# Shematic_NANO.net
KiCad netlist of a schematic drawn in Altium Designer
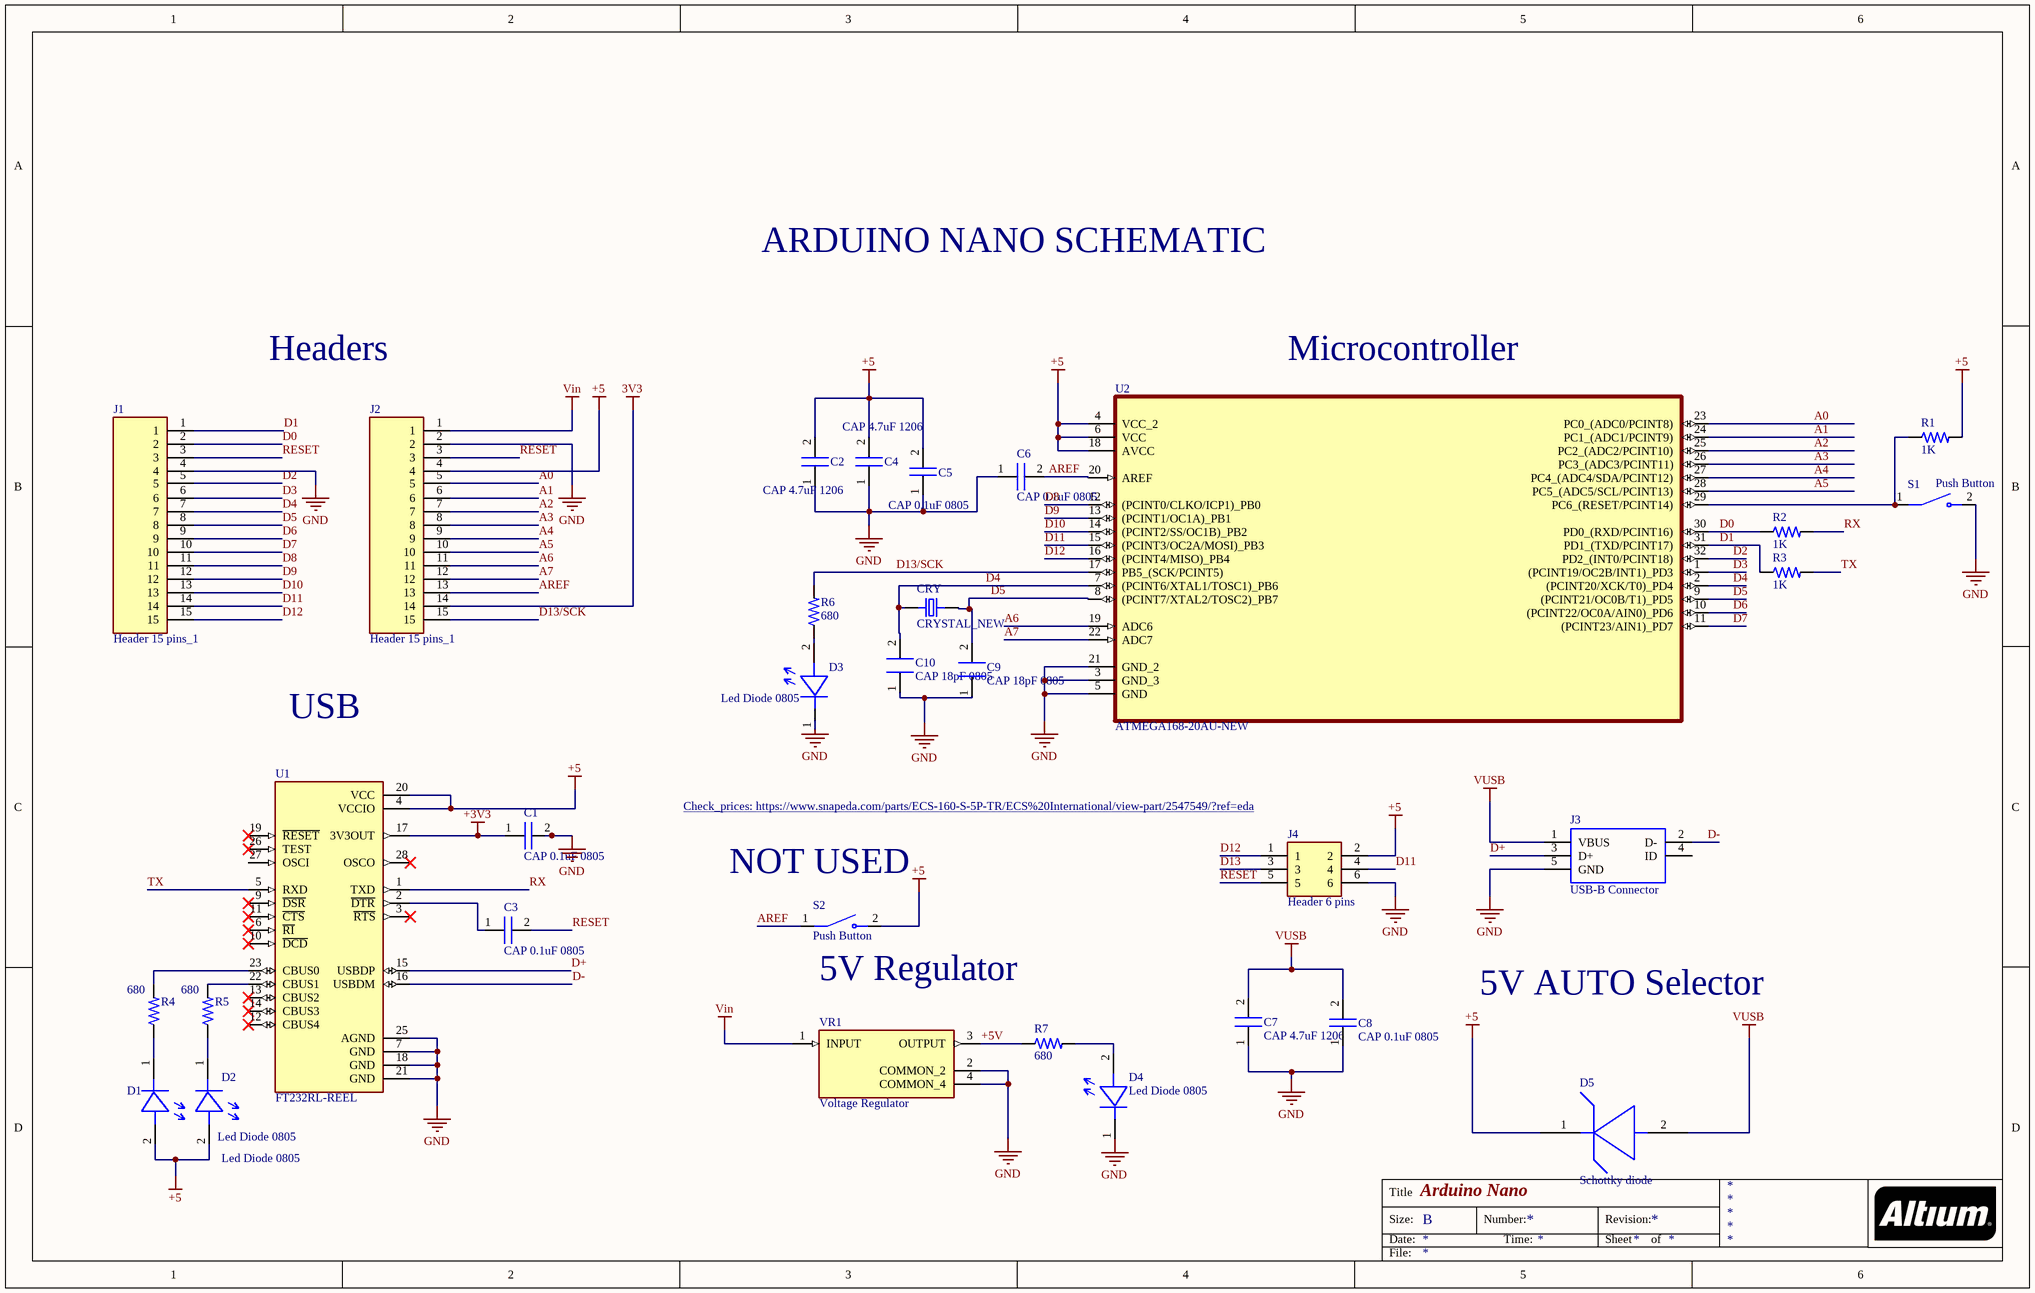
[diagram p0: Shematic_NANO.SchDoc]

(export (version "E")
  (design (tool "Eeschema 10.0.6"))
  (components
    (comp (ref "C1")
      (value "CAP 0.1uF 0805")
      (footprint "CAP 0.1uF 0805")
      (libsource (lib "Schlib1_NANO") (part "CAP 0.1uF 0805"))
    )
    (comp (ref "C2")
      (value "CAP 4.7uF 1206")
      (footprint "CAP 4.7 uF 1206")
      (libsource (lib "Schlib1_NANO") (part "CAP 4.7uF 1206"))
    )
    (comp (ref "C3")
      (value "CAP 0.1uF 0805")
      (footprint "CAP 0.1uF 0805")
      (libsource (lib "Schlib1_NANO") (part "CAP 0.1uF 0805"))
    )
    (comp (ref "C4")
      (value "CAP 4.7uF 1206")
      (footprint "CAP 4.7 uF 1206")
      (libsource (lib "Schlib1_NANO") (part "CAP 4.7uF 1206"))
    )
    (comp (ref "C5")
      (value "CAP 0.1uF 0805")
      (footprint "CAP 0.1uF 0805")
      (libsource (lib "Schlib1_NANO") (part "CAP 0.1uF 0805"))
    )
    (comp (ref "C6")
      (value "CAP 0.1uF 0805")
      (footprint "CAP 0.1uF 0805")
      (libsource (lib "Schlib1_NANO") (part "CAP 0.1uF 0805"))
    )
    (comp (ref "C7")
      (value "CAP 4.7uF 1206")
      (footprint "CAP 4.7 uF 1206")
      (libsource (lib "Schlib1_NANO") (part "CAP 4.7uF 1206"))
    )
    (comp (ref "C8")
      (value "CAP 0.1uF 0805")
      (footprint "CAP 0.1uF 0805")
      (libsource (lib "Schlib1_NANO") (part "CAP 0.1uF 0805"))
    )
    (comp (ref "C9")
      (value "CAP 18pF 0805")
      (footprint "CAP 18pF 0805")
      (libsource (lib "Schlib1_NANO") (part "CAP 18pF 0805"))
    )
    (comp (ref "C10")
      (value "CAP 18pF 0805")
      (footprint "CAP 18pF 0805")
      (libsource (lib "Schlib1_NANO") (part "CAP 18pF 0805"))
    )
    (comp (ref "CRY")
      (value "CRYSTAL_NEW")
      (footprint "CRYSTAL 16MHZ")
      (description "16MHz Â±30ppm Crystal Series 40 Ohms HC-49/US")
      (fields
        (field (name "MF") "ECS International")
        (field (name "MP") "ECS-160-S-5P-TR")
        (field (name "CHECK_PRICES") "https://www.snapeda.com/parts/ECS-160-S-5P-TR/ECS%20International/view-part/2547549/?ref=eda")
      )
      (libsource (lib "Schlib1_NANO") (part "CRYSTAL_NEW"))
    )
    (comp (ref "D1")
      (value "Led Diode 0805")
      (footprint "LED 0805")
      (libsource (lib "Schlib1_NANO") (part "Led Diode 0805"))
    )
    (comp (ref "D2")
      (value "Led Diode 0805")
      (footprint "LED 0805")
      (libsource (lib "Schlib1_NANO") (part "Led Diode 0805"))
    )
    (comp (ref "D3")
      (value "Led Diode 0805")
      (footprint "LED 0805")
      (libsource (lib "Schlib1_NANO") (part "Led Diode 0805"))
    )
    (comp (ref "D4")
      (value "Led Diode 0805")
      (footprint "LED 0805")
      (libsource (lib "Schlib1_NANO") (part "Led Diode 0805"))
    )
    (comp (ref "D5")
      (value "Schottky diode")
      (footprint "Schottky diode")
      (description "Schottky diode 0.5A 20V")
      (libsource (lib "Schlib1_NANO") (part "Schottky diode"))
    )
    (comp (ref "J1")
      (value "Header 15 pins_1")
      (footprint "Header 15 pins")
      (fields (field (name "MP") "4-644456-5"))
      (libsource (lib "Schlib1_NANO") (part "Header 15 pins_1"))
    )
    (comp (ref "J2")
      (value "Header 15 pins_1")
      (footprint "Header 15 pins")
      (fields (field (name "MP") "4-644456-5"))
      (libsource (lib "Schlib1_NANO") (part "Header 15 pins_1"))
    )
    (comp (ref "J3")
      (value "USB-B Connector")
      (footprint "USB-B Connector")
      (description "USB - mini B USB 2.0 OTG Receptacle Connector 5 Position Surface Mount, Right Angle")
      (fields (field (name "MF") "Molex") (field (name "MP") "67503-1020"))
      (libsource (lib "Schlib1_NANO") (part "USB-B Connector"))
    )
    (comp (ref "J4")
      (value "Header 6 pins")
      (footprint "Header 6 pins")
      (description "Connector Header Through Hole 6 position 0.100 _2.54mm_")
      (fields (field (name "MF") "Amphenol ICC") (field (name "DIGI-KEY_PART_NUMBER") "609-3234-ND"))
      (libsource (lib "Schlib1_NANO") (part "Header 6 pins"))
    )
    (comp (ref "R1")
      (value "1K")
      (footprint "RES 0402")
      (description "RL73H 2B R10 1% 5K RL")
      (fields (field (name "MP") "1-1879462-1"))
      (libsource (lib "Schlib1_NANO") (part "RES 1206"))
    )
    (comp (ref "R2")
      (value "1K")
      (footprint "RES 0402")
      (description "RL73H 2B R10 1% 5K RL")
      (fields (field (name "MP") "1-1879462-1"))
      (libsource (lib "Schlib1_NANO") (part "RES 1206"))
    )
    (comp (ref "R3")
      (value "1K")
      (footprint "RES 0402")
      (description "RL73H 2B R10 1% 5K RL")
      (fields (field (name "MP") "1-1879462-1"))
      (libsource (lib "Schlib1_NANO") (part "RES 1206"))
    )
    (comp (ref "R4")
      (value "680")
      (footprint "RES 0402")
      (description "RL73H 2B R10 1% 5K RL")
      (fields (field (name "MP") "1-1879462-1"))
      (libsource (lib "Schlib1_NANO") (part "RES 1206"))
    )
    (comp (ref "R5")
      (value "680")
      (footprint "RES 0402")
      (description "RL73H 2B R10 1% 5K RL")
      (fields (field (name "MP") "1-1879462-1"))
      (libsource (lib "Schlib1_NANO") (part "RES 1206"))
    )
    (comp (ref "R6")
      (value "680")
      (footprint "RES 0402")
      (description "RL73H 2B R10 1% 5K RL")
      (fields (field (name "MP") "1-1879462-1"))
      (libsource (lib "Schlib1_NANO") (part "RES 1206"))
    )
    (comp (ref "R7")
      (value "680")
      (footprint "RES 0402")
      (description "RL73H 2B R10 1% 5K RL")
      (fields (field (name "MP") "1-1879462-1"))
      (libsource (lib "Schlib1_NANO") (part "RES 1206"))
    )
    (comp (ref "S1")
      (value "Push Button")
      (footprint "Push Button")
      (description "Switch Tactile N.O. SPST Round Button Gull Wing 0.05A 12VDC 1.5N SMD Embossed T/R")
      (fields (field (name "MP") "B3U-1000P"))
      (libsource (lib "Schlib1_NANO") (part "Push Button"))
    )
    (comp (ref "S2")
      (value "Push Button")
      (footprint "Push Button")
      (description "Switch Tactile N.O. SPST Round Button Gull Wing 0.05A 12VDC 1.5N SMD Embossed T/R")
      (fields (field (name "MP") "B3U-1000P"))
      (libsource (lib "Schlib1_NANO") (part "Push Button"))
    )
    (comp (ref "U1")
      (value "FT232RL-REEL")
      (footprint "SOP65P780X200-28N")
      (description "USB Full Speed to Serial UART IC, Includes Oscillator and EEPROM - SSOP-28")
      (libsource (lib "Schlib1_NANO") (part "FT232RL-REEL"))
    )
    (comp (ref "U2")
      (value "ATMEGA168-20AU-NEW")
      (footprint "ATMEGA168-20AU - duplicate")
      (description "AVR AVRÂ® ATmega Microcontroller IC 8-Bit 20MHz 16KB _8K x 16_ FLASH 32-TQFP _7x7_")
      (fields (field (name "MP") "ATMEGA168-20AU") (field (name "MF") "Microchip"))
      (libsource (lib "Schlib1_NANO") (part "ATMEGA168-20AU-NEW"))
    )
    (comp (ref "VR1")
      (value "Voltage Regulator")
      (footprint "Voltage Regulator")
      (description "500-mA, 30-V, linear voltage regulator 4-SOT-223 0 to 125")
      (fields (field (name "MP") "UA78M05CDCYRG3") (field (name "MF") "Texas Instruments"))
      (libsource (lib "Schlib1_NANO") (part "Voltage Regulator"))
    )
  )
  (nets
    (net (code "1") (name "+3V3") (class "Default")
      (node (ref "C1") (pin "1") (pinfunction "1_1") (pintype "passive"))
      (node (ref "U1") (pin "17") (pinfunction "3V3OUT_17") (pintype "output"))
    )
    (net (code "2") (name "+5") (class "Default")
      (node (ref "C2") (pin "2") (pinfunction "2_2") (pintype "passive"))
      (node (ref "C4") (pin "2") (pinfunction "2_2") (pintype "passive"))
      (node (ref "C5") (pin "2") (pinfunction "2_2") (pintype "passive"))
      (node (ref "D1") (pin "2") (pinfunction "2_2") (pintype "passive"))
      (node (ref "D2") (pin "2") (pinfunction "2_2") (pintype "passive"))
      (node (ref "D5") (pin "1") (pinfunction "1_1") (pintype "passive"))
      (node (ref "J2") (pin "4") (pinfunction "4_4") (pintype "passive"))
      (node (ref "J4") (pin "2") (pinfunction "2_2") (pintype "passive"))
      (node (ref "R1") (pin "2") (pinfunction "2_2") (pintype "passive"))
      (node (ref "S2") (pin "2") (pinfunction "2_2") (pintype "passive"))
      (node (ref "U1") (pin "20") (pinfunction "VCC_20") (pintype "power_in"))
      (node (ref "U1") (pin "4") (pinfunction "VCCIO_4") (pintype "power_in"))
      (node (ref "U2") (pin "18") (pinfunction "AVCC_18") (pintype "power_in"))
      (node (ref "U2") (pin "4") (pinfunction "VCC_2_4") (pintype "power_in"))
      (node (ref "U2") (pin "6") (pinfunction "VCC_6") (pintype "power_in"))
    )
    (net (code "3") (name "/+5V") (class "Default")
      (node (ref "R7") (pin "1") (pinfunction "1_1") (pintype "passive"))
      (node (ref "VR1") (pin "3") (pinfunction "OUTPUT_3") (pintype "output"))
    )
    (net (code "4") (name "/A0") (class "Default")
      (node (ref "J2") (pin "5") (pinfunction "5_5") (pintype "passive"))
      (node (ref "U2") (pin "23") (pinfunction "PC0_(ADC0/PCINT8)_23") (pintype "bidirectional"))
    )
    (net (code "5") (name "/A1") (class "Default")
      (node (ref "J2") (pin "6") (pinfunction "6_6") (pintype "passive"))
      (node (ref "U2") (pin "24") (pinfunction "PC1_(ADC1/PCINT9)_24") (pintype "bidirectional"))
    )
    (net (code "6") (name "/A2") (class "Default")
      (node (ref "J2") (pin "7") (pinfunction "7_7") (pintype "passive"))
      (node (ref "U2") (pin "25") (pinfunction "PC2_(ADC2/PCINT10)_25") (pintype "bidirectional"))
    )
    (net (code "7") (name "/A3") (class "Default")
      (node (ref "J2") (pin "8") (pinfunction "8_8") (pintype "passive"))
      (node (ref "U2") (pin "26") (pinfunction "PC3_(ADC3/PCINT11)_26") (pintype "bidirectional"))
    )
    (net (code "8") (name "/A4") (class "Default")
      (node (ref "J2") (pin "9") (pinfunction "9_9") (pintype "passive"))
      (node (ref "U2") (pin "27") (pinfunction "PC4_(ADC4/SDA/PCINT12)_27") (pintype "bidirectional"))
    )
    (net (code "9") (name "/A5") (class "Default")
      (node (ref "J2") (pin "10") (pinfunction "10_10") (pintype "passive"))
      (node (ref "U2") (pin "28") (pinfunction "PC5_(ADC5/SCL/PCINT13)_28") (pintype "bidirectional"))
    )
    (net (code "10") (name "/A6") (class "Default")
      (node (ref "J2") (pin "11") (pinfunction "11_11") (pintype "passive"))
      (node (ref "U2") (pin "19") (pinfunction "ADC6_19") (pintype "input"))
    )
    (net (code "11") (name "/A7") (class "Default")
      (node (ref "J2") (pin "12") (pinfunction "12_12") (pintype "passive"))
      (node (ref "U2") (pin "22") (pinfunction "ADC7_22") (pintype "input"))
    )
    (net (code "12") (name "/AREF") (class "Default")
      (node (ref "C6") (pin "2") (pinfunction "2_2") (pintype "passive"))
      (node (ref "J2") (pin "13") (pinfunction "13_13") (pintype "passive"))
      (node (ref "S2") (pin "1") (pinfunction "1_1") (pintype "passive"))
      (node (ref "U2") (pin "20") (pinfunction "AREF_20") (pintype "input"))
    )
    (net (code "13") (name "/D+") (class "Default")
      (node (ref "J3") (pin "3") (pinfunction "D+_3") (pintype "passive"))
      (node (ref "U1") (pin "15") (pinfunction "USBDP_15") (pintype "bidirectional"))
    )
    (net (code "14") (name "/D-") (class "Default")
      (node (ref "J3") (pin "2") (pinfunction "D-_2") (pintype "passive"))
      (node (ref "U1") (pin "16") (pinfunction "USBDM_16") (pintype "bidirectional"))
    )
    (net (code "15") (name "/D0") (class "Default")
      (node (ref "J1") (pin "2") (pinfunction "2_2") (pintype "passive"))
      (node (ref "R2") (pin "1") (pinfunction "1_1") (pintype "passive"))
      (node (ref "U2") (pin "30") (pinfunction "PD0_(RXD/PCINT16)_30") (pintype "bidirectional"))
    )
    (net (code "16") (name "/D1") (class "Default")
      (node (ref "J1") (pin "1") (pinfunction "1_1") (pintype "passive"))
      (node (ref "R3") (pin "1") (pinfunction "1_1") (pintype "passive"))
      (node (ref "U2") (pin "31") (pinfunction "PD1_(TXD/PCINT17)_31") (pintype "bidirectional"))
    )
    (net (code "17") (name "/D2") (class "Default")
      (node (ref "J1") (pin "5") (pinfunction "5_5") (pintype "passive"))
      (node (ref "U2") (pin "32") (pinfunction "PD2_(INT0/PCINT18)_32") (pintype "bidirectional"))
    )
    (net (code "18") (name "/D3") (class "Default")
      (node (ref "J1") (pin "6") (pinfunction "6_6") (pintype "passive"))
      (node (ref "U2") (pin "1") (pinfunction "(PCINT19/OC2B/INT1)_PD3_1") (pintype "bidirectional"))
    )
    (net (code "19") (name "/D4") (class "Default")
      (node (ref "C10") (pin "2") (pinfunction "2_2") (pintype "passive"))
      (node (ref "CRY") (pin "1") (pinfunction "1_1") (pintype "passive"))
      (node (ref "J1") (pin "7") (pinfunction "7_7") (pintype "passive"))
      (node (ref "U2") (pin "2") (pinfunction "(PCINT20/XCK/T0)_PD4_2") (pintype "bidirectional"))
      (node (ref "U2") (pin "7") (pinfunction "(PCINT6/XTAL1/TOSC1)_PB6_7") (pintype "bidirectional"))
    )
    (net (code "20") (name "/D5") (class "Default")
      (node (ref "C9") (pin "2") (pinfunction "2_2") (pintype "passive"))
      (node (ref "CRY") (pin "2") (pinfunction "2_2") (pintype "passive"))
      (node (ref "J1") (pin "8") (pinfunction "8_8") (pintype "passive"))
      (node (ref "U2") (pin "8") (pinfunction "(PCINT7/XTAL2/TOSC2)_PB7_8") (pintype "bidirectional"))
      (node (ref "U2") (pin "9") (pinfunction "(PCINT21/OC0B/T1)_PD5_9") (pintype "bidirectional"))
    )
    (net (code "21") (name "/D6") (class "Default")
      (node (ref "J1") (pin "9") (pinfunction "9_9") (pintype "passive"))
      (node (ref "U2") (pin "10") (pinfunction "(PCINT22/OC0A/AIN0)_PD6_10") (pintype "bidirectional"))
    )
    (net (code "22") (name "/D7") (class "Default")
      (node (ref "J1") (pin "10") (pinfunction "10_10") (pintype "passive"))
      (node (ref "U2") (pin "11") (pinfunction "(PCINT23/AIN1)_PD7_11") (pintype "bidirectional"))
    )
    (net (code "23") (name "/D8") (class "Default")
      (node (ref "J1") (pin "11") (pinfunction "11_11") (pintype "passive"))
      (node (ref "U2") (pin "12") (pinfunction "(PCINT0/CLKO/ICP1)_PB0_12") (pintype "bidirectional"))
    )
    (net (code "24") (name "/D9") (class "Default")
      (node (ref "J1") (pin "12") (pinfunction "12_12") (pintype "passive"))
      (node (ref "U2") (pin "13") (pinfunction "(PCINT1/OC1A)_PB1_13") (pintype "bidirectional"))
    )
    (net (code "25") (name "/D10") (class "Default")
      (node (ref "J1") (pin "13") (pinfunction "13_13") (pintype "passive"))
      (node (ref "U2") (pin "14") (pinfunction "(PCINT2/SS/OC1B)_PB2_14") (pintype "bidirectional"))
    )
    (net (code "26") (name "/D11") (class "Default")
      (node (ref "J1") (pin "14") (pinfunction "14_14") (pintype "passive"))
      (node (ref "J4") (pin "4") (pinfunction "4_4") (pintype "passive"))
      (node (ref "U2") (pin "15") (pinfunction "(PCINT3/OC2A/MOSI)_PB3_15") (pintype "bidirectional"))
    )
    (net (code "27") (name "/D12") (class "Default")
      (node (ref "J1") (pin "15") (pinfunction "15_15") (pintype "passive"))
      (node (ref "J4") (pin "1") (pinfunction "1_1") (pintype "passive"))
      (node (ref "U2") (pin "16") (pinfunction "(PCINT4/MISO)_PB4_16") (pintype "bidirectional"))
    )
    (net (code "28") (name "/D13") (class "Default")
      (node (ref "J4") (pin "3") (pinfunction "3_3") (pintype "passive"))
    )
    (net (code "29") (name "/D13{slash}SCK") (class "Default")
      (node (ref "J2") (pin "15") (pinfunction "15_15") (pintype "passive"))
      (node (ref "R6") (pin "2") (pinfunction "2_2") (pintype "passive"))
      (node (ref "U2") (pin "17") (pinfunction "PB5_(SCK/PCINT5)_17") (pintype "bidirectional"))
    )
    (net (code "30") (name "/RESET") (class "Default")
      (node (ref "C3") (pin "2") (pinfunction "2_2") (pintype "passive"))
      (node (ref "J1") (pin "3") (pinfunction "3_3") (pintype "passive"))
      (node (ref "J2") (pin "3") (pinfunction "3_3") (pintype "passive"))
      (node (ref "J4") (pin "5") (pinfunction "5_5") (pintype "passive"))
    )
    (net (code "31") (name "/RX") (class "Default")
      (node (ref "R2") (pin "2") (pinfunction "2_2") (pintype "passive"))
      (node (ref "U1") (pin "1") (pinfunction "TXD_1") (pintype "output"))
    )
    (net (code "32") (name "/TX") (class "Default")
      (node (ref "R3") (pin "2") (pinfunction "2_2") (pintype "passive"))
      (node (ref "U1") (pin "5") (pinfunction "RXD_5") (pintype "input"))
    )
    (net (code "33") (name "3V3") (class "Default")
      (node (ref "J2") (pin "14") (pinfunction "14_14") (pintype "passive"))
    )
    (net (code "34") (name "GND") (class "Default")
      (node (ref "C1") (pin "2") (pinfunction "2_2") (pintype "passive"))
      (node (ref "C10") (pin "1") (pinfunction "1_1") (pintype "passive"))
      (node (ref "C2") (pin "1") (pinfunction "1_1") (pintype "passive"))
      (node (ref "C4") (pin "1") (pinfunction "1_1") (pintype "passive"))
      (node (ref "C5") (pin "1") (pinfunction "1_1") (pintype "passive"))
      (node (ref "C6") (pin "1") (pinfunction "1_1") (pintype "passive"))
      (node (ref "C7") (pin "1") (pinfunction "1_1") (pintype "passive"))
      (node (ref "C8") (pin "1") (pinfunction "1_1") (pintype "passive"))
      (node (ref "C9") (pin "1") (pinfunction "1_1") (pintype "passive"))
      (node (ref "D3") (pin "1") (pinfunction "1_1") (pintype "passive"))
      (node (ref "D4") (pin "1") (pinfunction "1_1") (pintype "passive"))
      (node (ref "J1") (pin "4") (pinfunction "4_4") (pintype "passive"))
      (node (ref "J2") (pin "2") (pinfunction "2_2") (pintype "passive"))
      (node (ref "J3") (pin "5") (pinfunction "GND_5") (pintype "passive"))
      (node (ref "J4") (pin "6") (pinfunction "6_6") (pintype "passive"))
      (node (ref "S1") (pin "2") (pinfunction "2_2") (pintype "passive"))
      (node (ref "U1") (pin "18") (pinfunction "GND_18") (pintype "power_in"))
      (node (ref "U1") (pin "21") (pinfunction "GND_21") (pintype "power_in"))
      (node (ref "U1") (pin "25") (pinfunction "AGND_25") (pintype "power_in"))
      (node (ref "U1") (pin "7") (pinfunction "GND_7") (pintype "power_in"))
      (node (ref "U2") (pin "21") (pinfunction "GND_2_21") (pintype "passive"))
      (node (ref "U2") (pin "3") (pinfunction "GND_3_3") (pintype "passive"))
      (node (ref "U2") (pin "5") (pinfunction "GND_5") (pintype "passive"))
      (node (ref "VR1") (pin "2") (pinfunction "COMMON_2_2") (pintype "power_in"))
      (node (ref "VR1") (pin "4") (pinfunction "COMMON_4_4") (pintype "power_in"))
    )
    (net (code "35") (name "Net-(D1-Pad1)") (class "Default")
      (node (ref "D1") (pin "1") (pinfunction "1_1") (pintype "passive"))
      (node (ref "R4") (pin "1") (pinfunction "1_1") (pintype "passive"))
    )
    (net (code "36") (name "Net-(D2-Pad1)") (class "Default")
      (node (ref "D2") (pin "1") (pinfunction "1_1") (pintype "passive"))
      (node (ref "R5") (pin "1") (pinfunction "1_1") (pintype "passive"))
    )
    (net (code "37") (name "Net-(D3-Pad2)") (class "Default")
      (node (ref "D3") (pin "2") (pinfunction "2_2") (pintype "passive"))
      (node (ref "R6") (pin "1") (pinfunction "1_1") (pintype "passive"))
    )
    (net (code "38") (name "Net-(D4-Pad2)") (class "Default")
      (node (ref "D4") (pin "2") (pinfunction "2_2") (pintype "passive"))
      (node (ref "R7") (pin "2") (pinfunction "2_2") (pintype "passive"))
    )
    (net (code "39") (name "Net-(U1-CBUS0)") (class "Default")
      (node (ref "R4") (pin "2") (pinfunction "2_2") (pintype "passive"))
      (node (ref "U1") (pin "23") (pinfunction "CBUS0_23") (pintype "bidirectional"))
    )
    (net (code "40") (name "Net-(U1-CBUS1)") (class "Default")
      (node (ref "R5") (pin "2") (pinfunction "2_2") (pintype "passive"))
      (node (ref "U1") (pin "22") (pinfunction "CBUS1_22") (pintype "bidirectional"))
    )
    (net (code "41") (name "Net-(U1-~{DTR})") (class "Default")
      (node (ref "C3") (pin "1") (pinfunction "1_1") (pintype "passive"))
      (node (ref "U1") (pin "2") (pinfunction "~{DTR}_2") (pintype "output"))
    )
    (net (code "42") (name "Net-(U2-PC6_(RESET{slash}PCINT14))") (class "Default")
      (node (ref "R1") (pin "1") (pinfunction "1_1") (pintype "passive"))
      (node (ref "S1") (pin "1") (pinfunction "1_1") (pintype "passive"))
      (node (ref "U2") (pin "29") (pinfunction "PC6_(RESET/PCINT14)_29") (pintype "bidirectional"))
    )
    (net (code "43") (name "VUSB") (class "Default")
      (node (ref "C7") (pin "2") (pinfunction "2_2") (pintype "passive"))
      (node (ref "C8") (pin "2") (pinfunction "2_2") (pintype "passive"))
      (node (ref "D5") (pin "2") (pinfunction "2_2") (pintype "passive"))
      (node (ref "J3") (pin "1") (pinfunction "VBUS_1") (pintype "passive"))
    )
    (net (code "44") (name "Vin") (class "Default")
      (node (ref "J2") (pin "1") (pinfunction "1_1") (pintype "passive"))
      (node (ref "VR1") (pin "1") (pinfunction "INPUT_1") (pintype "input"))
    )
    (net (code "45") (name "unconnected-(J3-ID-Pad4)") (class "Default")
      (node (ref "J3") (pin "4") (pinfunction "ID_4") (pintype "passive"))
    )
    (net (code "46") (name "unconnected-(U1-CBUS2-Pad13)") (class "Default")
      (node (ref "U1") (pin "13") (pinfunction "CBUS2_13") (pintype "bidirectional+no_connect"))
    )
    (net (code "47") (name "unconnected-(U1-CBUS3-Pad14)") (class "Default")
      (node (ref "U1") (pin "14") (pinfunction "CBUS3_14") (pintype "bidirectional+no_connect"))
    )
    (net (code "48") (name "unconnected-(U1-CBUS4-Pad12)") (class "Default")
      (node (ref "U1") (pin "12") (pinfunction "CBUS4_12") (pintype "bidirectional+no_connect"))
    )
    (net (code "49") (name "unconnected-(U1-OSCI-Pad27)") (class "Default")
      (node (ref "U1") (pin "27") (pinfunction "OSCI_27") (pintype "input"))
    )
    (net (code "50") (name "unconnected-(U1-OSCO-Pad28)") (class "Default")
      (node (ref "U1") (pin "28") (pinfunction "OSCO_28") (pintype "output+no_connect"))
    )
    (net (code "51") (name "unconnected-(U1-TEST-Pad26)") (class "Default")
      (node (ref "U1") (pin "26") (pinfunction "TEST_26") (pintype "input+no_connect"))
    )
    (net (code "52") (name "unconnected-(U1-~{CTS}-Pad11)") (class "Default")
      (node (ref "U1") (pin "11") (pinfunction "~{CTS}_11") (pintype "input+no_connect"))
    )
    (net (code "53") (name "unconnected-(U1-~{DCD}-Pad10)") (class "Default")
      (node (ref "U1") (pin "10") (pinfunction "~{DCD}_10") (pintype "input+no_connect"))
    )
    (net (code "54") (name "unconnected-(U1-~{DSR}-Pad9)") (class "Default")
      (node (ref "U1") (pin "9") (pinfunction "~{DSR}_9") (pintype "input+no_connect"))
    )
    (net (code "55") (name "unconnected-(U1-~{RESET}-Pad19)") (class "Default")
      (node (ref "U1") (pin "19") (pinfunction "~{RESET}_19") (pintype "input+no_connect"))
    )
    (net (code "56") (name "unconnected-(U1-~{RI}-Pad6)") (class "Default")
      (node (ref "U1") (pin "6") (pinfunction "~{RI}_6") (pintype "input+no_connect"))
    )
    (net (code "57") (name "unconnected-(U1-~{RTS}-Pad3)") (class "Default")
      (node (ref "U1") (pin "3") (pinfunction "~{RTS}_3") (pintype "output+no_connect"))
    )
  )
)
